# Timer.net
KiCad netlist of a schematic drawn in EAGLE
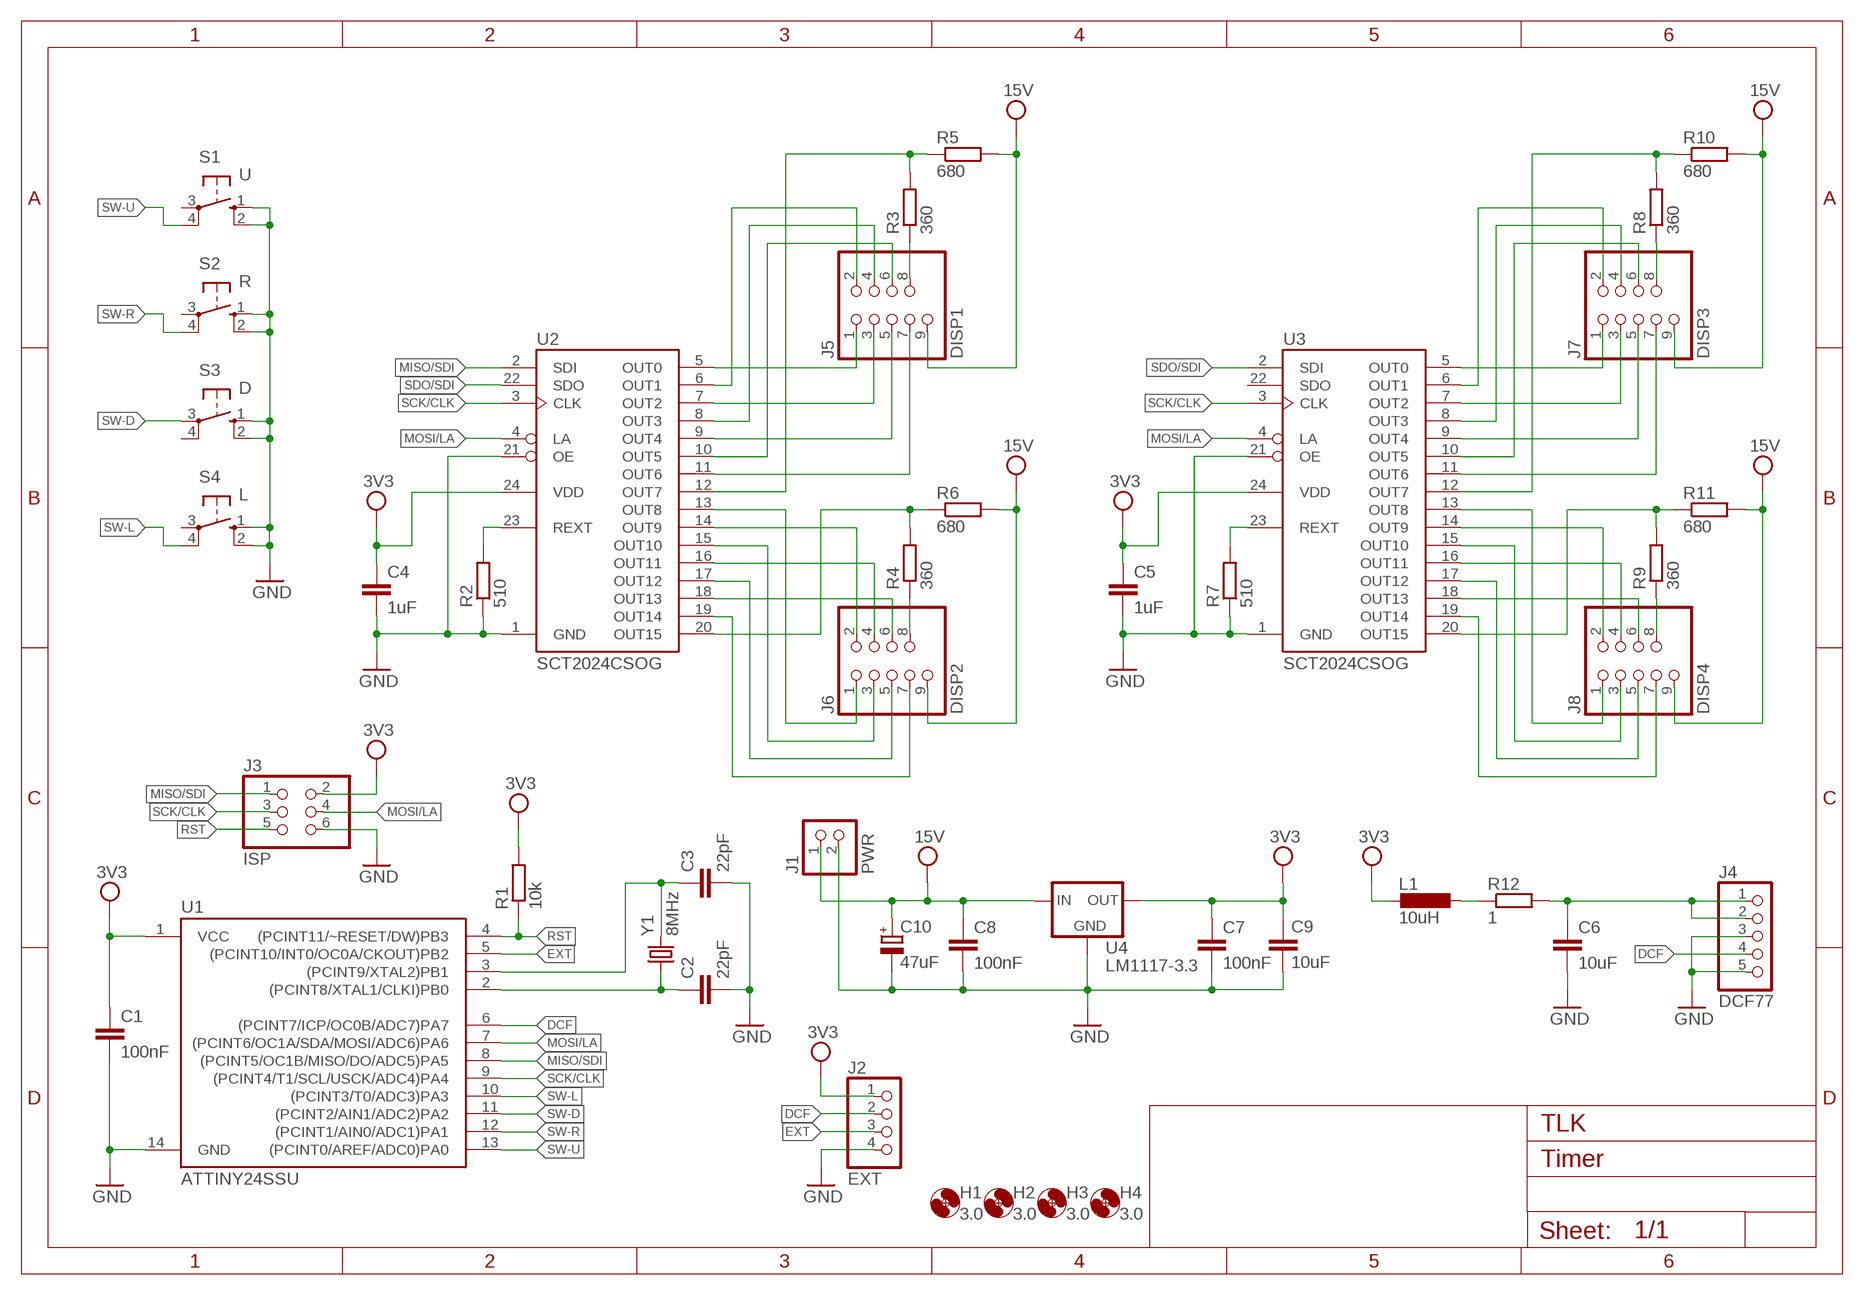
[diagram p0: schematic, sheet 1]

(export (version "E")
  (design (tool "Eeschema 10.0.6"))
  (components
    (comp (ref "C1")
      (value "100nF")
      (footprint "eagle-import:C0805")
      (libsource (lib "eagle-import") (part "C-EUC0805"))
    )
    (comp (ref "C2")
      (value "22pF")
      (footprint "eagle-import:C0805")
      (libsource (lib "eagle-import") (part "C-EUC0805"))
    )
    (comp (ref "C3")
      (value "22pF")
      (footprint "eagle-import:C0805")
      (libsource (lib "eagle-import") (part "C-EUC0805"))
    )
    (comp (ref "C4")
      (value "1uF")
      (footprint "eagle-import:C0805")
      (libsource (lib "eagle-import") (part "C-EUC0805"))
    )
    (comp (ref "C5")
      (value "1uF")
      (footprint "eagle-import:C0805")
      (libsource (lib "eagle-import") (part "C-EUC0805"))
    )
    (comp (ref "C6")
      (value "10uF")
      (footprint "eagle-import:C0805")
      (libsource (lib "eagle-import") (part "C-EUC0805"))
    )
    (comp (ref "C7")
      (value "100nF")
      (footprint "eagle-import:C0805")
      (libsource (lib "eagle-import") (part "C-EUC0805"))
    )
    (comp (ref "C8")
      (value "100nF")
      (footprint "eagle-import:C0805")
      (libsource (lib "eagle-import") (part "C-EUC0805"))
    )
    (comp (ref "C9")
      (value "10uF")
      (footprint "eagle-import:C0805")
      (libsource (lib "eagle-import") (part "C-EUC0805"))
    )
    (comp (ref "C10")
      (value "47uF")
      (footprint "eagle-import:E2,5")
      (libsource (lib "eagle-import") (part "CPOL-EUE2.5"))
    )
    (comp (ref "H1")
      (value "3.0")
      (footprint "eagle-import:3,0")
      (libsource (lib "eagle-import") (part "MOUNT-HOLE3.0"))
    )
    (comp (ref "H2")
      (value "3.0")
      (footprint "eagle-import:3,0")
      (libsource (lib "eagle-import") (part "MOUNT-HOLE3.0"))
    )
    (comp (ref "H3")
      (value "3.0")
      (footprint "eagle-import:3,0")
      (libsource (lib "eagle-import") (part "MOUNT-HOLE3.0"))
    )
    (comp (ref "H4")
      (value "3.0")
      (footprint "eagle-import:3,0")
      (libsource (lib "eagle-import") (part "MOUNT-HOLE3.0"))
    )
    (comp (ref "J1")
      (value "PWR")
      (footprint "eagle-import:1X02_90")
      (libsource (lib "eagle-import") (part "PINHD-1X2/90"))
    )
    (comp (ref "J2")
      (value "EXT")
      (footprint "eagle-import:1X04_90")
      (libsource (lib "eagle-import") (part "PINHD-1X4/90"))
    )
    (comp (ref "J3")
      (value "ISP")
      (footprint "eagle-import:2X03_90")
      (libsource (lib "eagle-import") (part "PINHD-2X3/90"))
    )
    (comp (ref "J4")
      (value "DCF77")
      (footprint "eagle-import:1X05_90")
      (libsource (lib "eagle-import") (part "PINHD-1X5/90"))
    )
    (comp (ref "J5")
      (value "DISP1")
      (footprint "eagle-import:2X04_05_90")
      (libsource (lib "eagle-import") (part "PINHD-2X4/5/90"))
    )
    (comp (ref "J6")
      (value "DISP2")
      (footprint "eagle-import:2X04_05_90")
      (libsource (lib "eagle-import") (part "PINHD-2X4/5/90"))
    )
    (comp (ref "J7")
      (value "DISP3")
      (footprint "eagle-import:2X04_05_90")
      (libsource (lib "eagle-import") (part "PINHD-2X4/5/90"))
    )
    (comp (ref "J8")
      (value "DISP4")
      (footprint "eagle-import:2X04_05_90")
      (libsource (lib "eagle-import") (part "PINHD-2X4/5/90"))
    )
    (comp (ref "L1")
      (value "10uH")
      (footprint "eagle-import:L0805")
      (libsource (lib "eagle-import") (part "L-EUL0805"))
    )
    (comp (ref "R1")
      (value "10k")
      (footprint "eagle-import:R0805")
      (libsource (lib "eagle-import") (part "R-EUR0805"))
    )
    (comp (ref "R2")
      (value "510")
      (footprint "eagle-import:R0805")
      (libsource (lib "eagle-import") (part "R-EUR0805"))
    )
    (comp (ref "R3")
      (value "360")
      (footprint "eagle-import:R1206")
      (libsource (lib "eagle-import") (part "R-EUR1206"))
    )
    (comp (ref "R4")
      (value "360")
      (footprint "eagle-import:R1206")
      (libsource (lib "eagle-import") (part "R-EUR1206"))
    )
    (comp (ref "R5")
      (value "680")
      (footprint "eagle-import:R1206")
      (libsource (lib "eagle-import") (part "R-EUR1206"))
    )
    (comp (ref "R6")
      (value "680")
      (footprint "eagle-import:R1206")
      (libsource (lib "eagle-import") (part "R-EUR1206"))
    )
    (comp (ref "R7")
      (value "510")
      (footprint "eagle-import:R0805")
      (libsource (lib "eagle-import") (part "R-EUR0805"))
    )
    (comp (ref "R8")
      (value "360")
      (footprint "eagle-import:R1206")
      (libsource (lib "eagle-import") (part "R-EUR1206"))
    )
    (comp (ref "R9")
      (value "360")
      (footprint "eagle-import:R1206")
      (libsource (lib "eagle-import") (part "R-EUR1206"))
    )
    (comp (ref "R10")
      (value "680")
      (footprint "eagle-import:R1206")
      (libsource (lib "eagle-import") (part "R-EUR1206"))
    )
    (comp (ref "R11")
      (value "680")
      (footprint "eagle-import:R1206")
      (libsource (lib "eagle-import") (part "R-EUR1206"))
    )
    (comp (ref "R12")
      (value "1")
      (footprint "eagle-import:R0805")
      (libsource (lib "eagle-import") (part "R-EUR0805"))
    )
    (comp (ref "S1")
      (value "U")
      (footprint "eagle-import:TACT-12")
      (libsource (lib "eagle-import") (part "TACT"))
    )
    (comp (ref "S2")
      (value "R")
      (footprint "eagle-import:TACT-12")
      (libsource (lib "eagle-import") (part "TACT"))
    )
    (comp (ref "S3")
      (value "D")
      (footprint "eagle-import:TACT-12")
      (libsource (lib "eagle-import") (part "TACT"))
    )
    (comp (ref "S4")
      (value "L")
      (footprint "eagle-import:TACT-12")
      (libsource (lib "eagle-import") (part "TACT"))
    )
    (comp (ref "U1")
      (value "ATTINY24SSU")
      (footprint "eagle-import:SO14")
      (libsource (lib "eagle-import") (part "ATTINY24SSU"))
    )
    (comp (ref "U2")
      (value "SCT2024CSOG")
      (footprint "eagle-import:SO24W")
      (libsource (lib "eagle-import") (part "SCT2024CSOG"))
    )
    (comp (ref "U3")
      (value "SCT2024CSOG")
      (footprint "eagle-import:SO24W")
      (libsource (lib "eagle-import") (part "SCT2024CSOG"))
    )
    (comp (ref "U4")
      (value "LM1117-3.3")
      (footprint "eagle-import:SOT223")
      (libsource (lib "eagle-import") (part "LM1117-3.3"))
    )
    (comp (ref "Y1")
      (value "8MHz")
      (footprint "eagle-import:HC49UP")
      (libsource (lib "eagle-import") (part "CRYSTALHC49UP"))
    )
  )
  (nets
    (net (code "1") (name "3V3") (class "Default")
      (node (ref "C1") (pin "1") (pinfunction "1_1") (pintype "passive"))
      (node (ref "C4") (pin "1") (pinfunction "1_1") (pintype "passive"))
      (node (ref "C5") (pin "1") (pinfunction "1_1") (pintype "passive"))
      (node (ref "C7") (pin "1") (pinfunction "1_1") (pintype "passive"))
      (node (ref "C9") (pin "1") (pinfunction "1_1") (pintype "passive"))
      (node (ref "J2") (pin "1") (pinfunction "1_1") (pintype "passive"))
      (node (ref "J3") (pin "2") (pinfunction "2_2") (pintype "passive"))
      (node (ref "L1") (pin "2") (pinfunction "2_2") (pintype "passive"))
      (node (ref "R1") (pin "2") (pinfunction "2_2") (pintype "passive"))
      (node (ref "U1") (pin "1") (pinfunction "VCC_1") (pintype "bidirectional"))
      (node (ref "U2") (pin "24") (pinfunction "VDD_24") (pintype "power_in"))
      (node (ref "U3") (pin "24") (pinfunction "VDD_24") (pintype "power_in"))
      (node (ref "U4") (pin "2") (pinfunction "OUT_2") (pintype "passive"))
      (node (ref "U4") (pin "4") (pinfunction "OUT_4") (pintype "passive"))
    )
    (net (code "2") (name "15V") (class "Default")
      (node (ref "C10") (pin "+") (pinfunction "+_+") (pintype "passive"))
      (node (ref "C8") (pin "1") (pinfunction "1_1") (pintype "passive"))
      (node (ref "J1") (pin "1") (pinfunction "1_1") (pintype "passive"))
      (node (ref "J5") (pin "9") (pinfunction "9_9") (pintype "passive"))
      (node (ref "J6") (pin "9") (pinfunction "9_9") (pintype "passive"))
      (node (ref "J7") (pin "9") (pinfunction "9_9") (pintype "passive"))
      (node (ref "J8") (pin "9") (pinfunction "9_9") (pintype "passive"))
      (node (ref "R10") (pin "2") (pinfunction "2_2") (pintype "passive"))
      (node (ref "R11") (pin "2") (pinfunction "2_2") (pintype "passive"))
      (node (ref "R5") (pin "2") (pinfunction "2_2") (pintype "passive"))
      (node (ref "R6") (pin "2") (pinfunction "2_2") (pintype "passive"))
      (node (ref "U4") (pin "3") (pinfunction "IN_3") (pintype "input"))
    )
    (net (code "3") (name "DCF") (class "Default")
      (node (ref "J2") (pin "2") (pinfunction "2_2") (pintype "passive"))
      (node (ref "J4") (pin "4") (pinfunction "4_4") (pintype "passive"))
      (node (ref "U1") (pin "6") (pinfunction "(PCINT7/ICP/OC0B/ADC7)PA7_6") (pintype "bidirectional"))
    )
    (net (code "4") (name "EXT") (class "Default")
      (node (ref "J2") (pin "3") (pinfunction "3_3") (pintype "passive"))
      (node (ref "U1") (pin "5") (pinfunction "(PCINT10/INT0/OC0A/CKOUT)PB2_5") (pintype "bidirectional"))
    )
    (net (code "5") (name "GND") (class "Default")
      (node (ref "C1") (pin "2") (pinfunction "2_2") (pintype "passive"))
      (node (ref "C10") (pin "-") (pinfunction "-_-") (pintype "passive"))
      (node (ref "C2") (pin "2") (pinfunction "2_2") (pintype "passive"))
      (node (ref "C3") (pin "2") (pinfunction "2_2") (pintype "passive"))
      (node (ref "C4") (pin "2") (pinfunction "2_2") (pintype "passive"))
      (node (ref "C5") (pin "2") (pinfunction "2_2") (pintype "passive"))
      (node (ref "C6") (pin "2") (pinfunction "2_2") (pintype "passive"))
      (node (ref "C7") (pin "2") (pinfunction "2_2") (pintype "passive"))
      (node (ref "C8") (pin "2") (pinfunction "2_2") (pintype "passive"))
      (node (ref "C9") (pin "2") (pinfunction "2_2") (pintype "passive"))
      (node (ref "J1") (pin "2") (pinfunction "2_2") (pintype "passive"))
      (node (ref "J2") (pin "4") (pinfunction "4_4") (pintype "passive"))
      (node (ref "J3") (pin "6") (pinfunction "6_6") (pintype "passive"))
      (node (ref "J4") (pin "3") (pinfunction "3_3") (pintype "passive"))
      (node (ref "J4") (pin "5") (pinfunction "5_5") (pintype "passive"))
      (node (ref "R2") (pin "1") (pinfunction "1_1") (pintype "passive"))
      (node (ref "R7") (pin "1") (pinfunction "1_1") (pintype "passive"))
      (node (ref "S1") (pin "1") (pinfunction "S_1") (pintype "passive"))
      (node (ref "S1") (pin "2") (pinfunction "S1_2") (pintype "passive"))
      (node (ref "S2") (pin "1") (pinfunction "S_1") (pintype "passive"))
      (node (ref "S2") (pin "2") (pinfunction "S1_2") (pintype "passive"))
      (node (ref "S3") (pin "1") (pinfunction "S_1") (pintype "passive"))
      (node (ref "S3") (pin "2") (pinfunction "S1_2") (pintype "passive"))
      (node (ref "S4") (pin "1") (pinfunction "S_1") (pintype "passive"))
      (node (ref "S4") (pin "2") (pinfunction "S1_2") (pintype "passive"))
      (node (ref "U1") (pin "14") (pinfunction "GND_14") (pintype "bidirectional"))
      (node (ref "U2") (pin "1") (pinfunction "GND_1") (pintype "power_in"))
      (node (ref "U2") (pin "21") (pinfunction "OE_21") (pintype "input"))
      (node (ref "U3") (pin "1") (pinfunction "GND_1") (pintype "power_in"))
      (node (ref "U3") (pin "21") (pinfunction "OE_21") (pintype "input"))
      (node (ref "U4") (pin "1") (pinfunction "GND_1") (pintype "input"))
    )
    (net (code "6") (name "MISO{slash}SDI") (class "Default")
      (node (ref "J3") (pin "1") (pinfunction "1_1") (pintype "passive"))
      (node (ref "U1") (pin "8") (pinfunction "(PCINT5/OC1B/MISO/DO/ADC5)PA5_8") (pintype "bidirectional"))
      (node (ref "U2") (pin "2") (pinfunction "SDI_2") (pintype "input"))
    )
    (net (code "7") (name "MOSI{slash}LA") (class "Default")
      (node (ref "J3") (pin "4") (pinfunction "4_4") (pintype "passive"))
      (node (ref "U1") (pin "7") (pinfunction "(PCINT6/OC1A/SDA/MOSI/ADC6)PA6_7") (pintype "bidirectional"))
      (node (ref "U2") (pin "4") (pinfunction "LA_4") (pintype "input"))
      (node (ref "U3") (pin "4") (pinfunction "LA_4") (pintype "input"))
    )
    (net (code "8") (name "Net-(C6-Pad1)") (class "Default")
      (node (ref "C6") (pin "1") (pinfunction "1_1") (pintype "passive"))
      (node (ref "J4") (pin "1") (pinfunction "1_1") (pintype "passive"))
      (node (ref "J4") (pin "2") (pinfunction "2_2") (pintype "passive"))
      (node (ref "R12") (pin "2") (pinfunction "2_2") (pintype "passive"))
    )
    (net (code "9") (name "Net-(J5-Pad8)") (class "Default")
      (node (ref "J5") (pin "8") (pinfunction "8_8") (pintype "passive"))
      (node (ref "R3") (pin "1") (pinfunction "1_1") (pintype "passive"))
    )
    (net (code "10") (name "Net-(J6-Pad8)") (class "Default")
      (node (ref "J6") (pin "8") (pinfunction "8_8") (pintype "passive"))
      (node (ref "R4") (pin "1") (pinfunction "1_1") (pintype "passive"))
    )
    (net (code "11") (name "Net-(J7-Pad8)") (class "Default")
      (node (ref "J7") (pin "8") (pinfunction "8_8") (pintype "passive"))
      (node (ref "R8") (pin "1") (pinfunction "1_1") (pintype "passive"))
    )
    (net (code "12") (name "Net-(J8-Pad8)") (class "Default")
      (node (ref "J8") (pin "8") (pinfunction "8_8") (pintype "passive"))
      (node (ref "R9") (pin "1") (pinfunction "1_1") (pintype "passive"))
    )
    (net (code "13") (name "Net-(L1-Pad1)") (class "Default")
      (node (ref "L1") (pin "1") (pinfunction "1_1") (pintype "passive"))
      (node (ref "R12") (pin "1") (pinfunction "1_1") (pintype "passive"))
    )
    (net (code "14") (name "Net-(U1-(PCINT8{slash}XTAL1{slash}CLKI)PB0)") (class "Default")
      (node (ref "C2") (pin "1") (pinfunction "1_1") (pintype "passive"))
      (node (ref "U1") (pin "2") (pinfunction "(PCINT8/XTAL1/CLKI)PB0_2") (pintype "bidirectional"))
      (node (ref "Y1") (pin "1") (pinfunction "1_1") (pintype "passive"))
    )
    (net (code "15") (name "Net-(U1-(PCINT9{slash}XTAL2)PB1)") (class "Default")
      (node (ref "C3") (pin "1") (pinfunction "1_1") (pintype "passive"))
      (node (ref "U1") (pin "3") (pinfunction "(PCINT9/XTAL2)PB1_3") (pintype "bidirectional"))
      (node (ref "Y1") (pin "2") (pinfunction "2_2") (pintype "passive"))
    )
    (net (code "16") (name "Net-(U2-OUT0)") (class "Default")
      (node (ref "J5") (pin "1") (pinfunction "1_1") (pintype "passive"))
      (node (ref "U2") (pin "5") (pinfunction "OUT0_5") (pintype "output"))
    )
    (net (code "17") (name "Net-(U2-OUT1)") (class "Default")
      (node (ref "J5") (pin "2") (pinfunction "2_2") (pintype "passive"))
      (node (ref "U2") (pin "6") (pinfunction "OUT1_6") (pintype "output"))
    )
    (net (code "18") (name "Net-(U2-OUT2)") (class "Default")
      (node (ref "J5") (pin "3") (pinfunction "3_3") (pintype "passive"))
      (node (ref "U2") (pin "7") (pinfunction "OUT2_7") (pintype "output"))
    )
    (net (code "19") (name "Net-(U2-OUT3)") (class "Default")
      (node (ref "J5") (pin "4") (pinfunction "4_4") (pintype "passive"))
      (node (ref "U2") (pin "8") (pinfunction "OUT3_8") (pintype "output"))
    )
    (net (code "20") (name "Net-(U2-OUT4)") (class "Default")
      (node (ref "J5") (pin "5") (pinfunction "5_5") (pintype "passive"))
      (node (ref "U2") (pin "9") (pinfunction "OUT4_9") (pintype "output"))
    )
    (net (code "21") (name "Net-(U2-OUT5)") (class "Default")
      (node (ref "J5") (pin "6") (pinfunction "6_6") (pintype "passive"))
      (node (ref "U2") (pin "10") (pinfunction "OUT5_10") (pintype "output"))
    )
    (net (code "22") (name "Net-(U2-OUT6)") (class "Default")
      (node (ref "J5") (pin "7") (pinfunction "7_7") (pintype "passive"))
      (node (ref "U2") (pin "11") (pinfunction "OUT6_11") (pintype "output"))
    )
    (net (code "23") (name "Net-(U2-OUT7)") (class "Default")
      (node (ref "R3") (pin "2") (pinfunction "2_2") (pintype "passive"))
      (node (ref "R5") (pin "1") (pinfunction "1_1") (pintype "passive"))
      (node (ref "U2") (pin "12") (pinfunction "OUT7_12") (pintype "output"))
    )
    (net (code "24") (name "Net-(U2-OUT8)") (class "Default")
      (node (ref "J6") (pin "1") (pinfunction "1_1") (pintype "passive"))
      (node (ref "U2") (pin "13") (pinfunction "OUT8_13") (pintype "output"))
    )
    (net (code "25") (name "Net-(U2-OUT9)") (class "Default")
      (node (ref "J6") (pin "2") (pinfunction "2_2") (pintype "passive"))
      (node (ref "U2") (pin "14") (pinfunction "OUT9_14") (pintype "output"))
    )
    (net (code "26") (name "Net-(U2-OUT10)") (class "Default")
      (node (ref "J6") (pin "3") (pinfunction "3_3") (pintype "passive"))
      (node (ref "U2") (pin "15") (pinfunction "OUT10_15") (pintype "output"))
    )
    (net (code "27") (name "Net-(U2-OUT11)") (class "Default")
      (node (ref "J6") (pin "4") (pinfunction "4_4") (pintype "passive"))
      (node (ref "U2") (pin "16") (pinfunction "OUT11_16") (pintype "output"))
    )
    (net (code "28") (name "Net-(U2-OUT12)") (class "Default")
      (node (ref "J6") (pin "5") (pinfunction "5_5") (pintype "passive"))
      (node (ref "U2") (pin "17") (pinfunction "OUT12_17") (pintype "output"))
    )
    (net (code "29") (name "Net-(U2-OUT13)") (class "Default")
      (node (ref "J6") (pin "6") (pinfunction "6_6") (pintype "passive"))
      (node (ref "U2") (pin "18") (pinfunction "OUT13_18") (pintype "output"))
    )
    (net (code "30") (name "Net-(U2-OUT14)") (class "Default")
      (node (ref "J6") (pin "7") (pinfunction "7_7") (pintype "passive"))
      (node (ref "U2") (pin "19") (pinfunction "OUT14_19") (pintype "output"))
    )
    (net (code "31") (name "Net-(U2-OUT15)") (class "Default")
      (node (ref "R4") (pin "2") (pinfunction "2_2") (pintype "passive"))
      (node (ref "R6") (pin "1") (pinfunction "1_1") (pintype "passive"))
      (node (ref "U2") (pin "20") (pinfunction "OUT15_20") (pintype "output"))
    )
    (net (code "32") (name "Net-(U2-REXT)") (class "Default")
      (node (ref "R2") (pin "2") (pinfunction "2_2") (pintype "passive"))
      (node (ref "U2") (pin "23") (pinfunction "REXT_23") (pintype "passive"))
    )
    (net (code "33") (name "Net-(U3-OUT0)") (class "Default")
      (node (ref "J7") (pin "1") (pinfunction "1_1") (pintype "passive"))
      (node (ref "U3") (pin "5") (pinfunction "OUT0_5") (pintype "output"))
    )
    (net (code "34") (name "Net-(U3-OUT1)") (class "Default")
      (node (ref "J7") (pin "2") (pinfunction "2_2") (pintype "passive"))
      (node (ref "U3") (pin "6") (pinfunction "OUT1_6") (pintype "output"))
    )
    (net (code "35") (name "Net-(U3-OUT2)") (class "Default")
      (node (ref "J7") (pin "3") (pinfunction "3_3") (pintype "passive"))
      (node (ref "U3") (pin "7") (pinfunction "OUT2_7") (pintype "output"))
    )
    (net (code "36") (name "Net-(U3-OUT3)") (class "Default")
      (node (ref "J7") (pin "4") (pinfunction "4_4") (pintype "passive"))
      (node (ref "U3") (pin "8") (pinfunction "OUT3_8") (pintype "output"))
    )
    (net (code "37") (name "Net-(U3-OUT4)") (class "Default")
      (node (ref "J7") (pin "5") (pinfunction "5_5") (pintype "passive"))
      (node (ref "U3") (pin "9") (pinfunction "OUT4_9") (pintype "output"))
    )
    (net (code "38") (name "Net-(U3-OUT5)") (class "Default")
      (node (ref "J7") (pin "6") (pinfunction "6_6") (pintype "passive"))
      (node (ref "U3") (pin "10") (pinfunction "OUT5_10") (pintype "output"))
    )
    (net (code "39") (name "Net-(U3-OUT6)") (class "Default")
      (node (ref "J7") (pin "7") (pinfunction "7_7") (pintype "passive"))
      (node (ref "U3") (pin "11") (pinfunction "OUT6_11") (pintype "output"))
    )
    (net (code "40") (name "Net-(U3-OUT7)") (class "Default")
      (node (ref "R10") (pin "1") (pinfunction "1_1") (pintype "passive"))
      (node (ref "R8") (pin "2") (pinfunction "2_2") (pintype "passive"))
      (node (ref "U3") (pin "12") (pinfunction "OUT7_12") (pintype "output"))
    )
    (net (code "41") (name "Net-(U3-OUT8)") (class "Default")
      (node (ref "J8") (pin "1") (pinfunction "1_1") (pintype "passive"))
      (node (ref "U3") (pin "13") (pinfunction "OUT8_13") (pintype "output"))
    )
    (net (code "42") (name "Net-(U3-OUT9)") (class "Default")
      (node (ref "J8") (pin "2") (pinfunction "2_2") (pintype "passive"))
      (node (ref "U3") (pin "14") (pinfunction "OUT9_14") (pintype "output"))
    )
    (net (code "43") (name "Net-(U3-OUT10)") (class "Default")
      (node (ref "J8") (pin "3") (pinfunction "3_3") (pintype "passive"))
      (node (ref "U3") (pin "15") (pinfunction "OUT10_15") (pintype "output"))
    )
    (net (code "44") (name "Net-(U3-OUT11)") (class "Default")
      (node (ref "J8") (pin "4") (pinfunction "4_4") (pintype "passive"))
      (node (ref "U3") (pin "16") (pinfunction "OUT11_16") (pintype "output"))
    )
    (net (code "45") (name "Net-(U3-OUT12)") (class "Default")
      (node (ref "J8") (pin "5") (pinfunction "5_5") (pintype "passive"))
      (node (ref "U3") (pin "17") (pinfunction "OUT12_17") (pintype "output"))
    )
    (net (code "46") (name "Net-(U3-OUT13)") (class "Default")
      (node (ref "J8") (pin "6") (pinfunction "6_6") (pintype "passive"))
      (node (ref "U3") (pin "18") (pinfunction "OUT13_18") (pintype "output"))
    )
    (net (code "47") (name "Net-(U3-OUT14)") (class "Default")
      (node (ref "J8") (pin "7") (pinfunction "7_7") (pintype "passive"))
      (node (ref "U3") (pin "19") (pinfunction "OUT14_19") (pintype "output"))
    )
    (net (code "48") (name "Net-(U3-OUT15)") (class "Default")
      (node (ref "R11") (pin "1") (pinfunction "1_1") (pintype "passive"))
      (node (ref "R9") (pin "2") (pinfunction "2_2") (pintype "passive"))
      (node (ref "U3") (pin "20") (pinfunction "OUT15_20") (pintype "output"))
    )
    (net (code "49") (name "Net-(U3-REXT)") (class "Default")
      (node (ref "R7") (pin "2") (pinfunction "2_2") (pintype "passive"))
      (node (ref "U3") (pin "23") (pinfunction "REXT_23") (pintype "passive"))
    )
    (net (code "50") (name "RST") (class "Default")
      (node (ref "J3") (pin "5") (pinfunction "5_5") (pintype "passive"))
      (node (ref "R1") (pin "1") (pinfunction "1_1") (pintype "passive"))
      (node (ref "U1") (pin "4") (pinfunction "(PCINT11/~{RESET/DW})PB3_4") (pintype "bidirectional"))
    )
    (net (code "51") (name "SCK{slash}CLK") (class "Default")
      (node (ref "J3") (pin "3") (pinfunction "3_3") (pintype "passive"))
      (node (ref "U1") (pin "9") (pinfunction "(PCINT4/T1/SCL/USCK/ADC4)PA4_9") (pintype "bidirectional"))
      (node (ref "U2") (pin "3") (pinfunction "CLK_3") (pintype "input"))
      (node (ref "U3") (pin "3") (pinfunction "CLK_3") (pintype "input"))
    )
    (net (code "52") (name "SDO{slash}SDI") (class "Default")
      (node (ref "U2") (pin "22") (pinfunction "SDO_22") (pintype "output"))
      (node (ref "U3") (pin "2") (pinfunction "SDI_2") (pintype "input"))
    )
    (net (code "53") (name "SW-D") (class "Default")
      (node (ref "S3") (pin "3") (pinfunction "P_3") (pintype "passive"))
      (node (ref "U1") (pin "11") (pinfunction "(PCINT2/AIN1/ADC2)PA2_11") (pintype "bidirectional"))
    )
    (net (code "54") (name "SW-L") (class "Default")
      (node (ref "S4") (pin "4") (pinfunction "P1_4") (pintype "passive"))
      (node (ref "U1") (pin "10") (pinfunction "(PCINT3/T0/ADC3)PA3_10") (pintype "bidirectional"))
    )
    (net (code "55") (name "SW-R") (class "Default")
      (node (ref "S2") (pin "4") (pinfunction "P1_4") (pintype "passive"))
      (node (ref "U1") (pin "12") (pinfunction "(PCINT1/AIN0/ADC1)PA1_12") (pintype "bidirectional"))
    )
    (net (code "56") (name "SW-U") (class "Default")
      (node (ref "S1") (pin "4") (pinfunction "P1_4") (pintype "passive"))
      (node (ref "U1") (pin "13") (pinfunction "(PCINT0/AREF/ADC0)PA0_13") (pintype "bidirectional"))
    )
    (net (code "57") (name "unconnected-(S1-P-Pad3)") (class "Default")
      (node (ref "S1") (pin "3") (pinfunction "P_3") (pintype "passive"))
    )
    (net (code "58") (name "unconnected-(S2-P-Pad3)") (class "Default")
      (node (ref "S2") (pin "3") (pinfunction "P_3") (pintype "passive"))
    )
    (net (code "59") (name "unconnected-(S3-P1-Pad4)") (class "Default")
      (node (ref "S3") (pin "4") (pinfunction "P1_4") (pintype "passive"))
    )
    (net (code "60") (name "unconnected-(S4-P-Pad3)") (class "Default")
      (node (ref "S4") (pin "3") (pinfunction "P_3") (pintype "passive"))
    )
    (net (code "61") (name "unconnected-(U3-SDO-Pad22)") (class "Default")
      (node (ref "U3") (pin "22") (pinfunction "SDO_22") (pintype "output"))
    )
  )
)
